# TargetBoardResistiveDivider.net
KiCad netlist of a schematic drawn in EAGLE
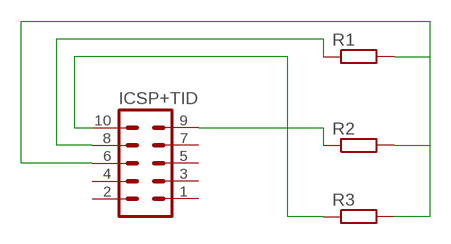
[diagram p0: schematic, sheet 1]

(export (version "E")
  (design (tool "Eeschema 10.0.6"))
  (components
    (comp (ref "ICSP+TID")
      (value "MA05-2")
      (footprint "eagle-import:MA05-2")
      (libsource (lib "eagle-import") (part "MA05-2"))
    )
    (comp (ref "R1")
      (value "R-EU_R1206")
      (footprint "eagle-import:R1206")
      (libsource (lib "eagle-import") (part "R-EU_R1206"))
    )
    (comp (ref "R2")
      (value "R-EU_R1206")
      (footprint "eagle-import:R1206")
      (libsource (lib "eagle-import") (part "R-EU_R1206"))
    )
    (comp (ref "R3")
      (value "R-EU_R1206")
      (footprint "eagle-import:R1206")
      (libsource (lib "eagle-import") (part "R-EU_R1206"))
    )
  )
  (nets
    (net (code "1") (name "Net-(ICSP+TID-Pad6)") (class "Default")
      (node (ref "ICSP+TID") (pin "6") (pinfunction "6_6") (pintype "passive"))
      (node (ref "R1") (pin "2") (pinfunction "2_2") (pintype "passive"))
      (node (ref "R2") (pin "2") (pinfunction "2_2") (pintype "passive"))
      (node (ref "R3") (pin "2") (pinfunction "2_2") (pintype "passive"))
    )
    (net (code "2") (name "Net-(ICSP+TID-Pad8)") (class "Default")
      (node (ref "ICSP+TID") (pin "8") (pinfunction "8_8") (pintype "passive"))
      (node (ref "R1") (pin "1") (pinfunction "1_1") (pintype "passive"))
    )
    (net (code "3") (name "Net-(ICSP+TID-Pad9)") (class "Default")
      (node (ref "ICSP+TID") (pin "9") (pinfunction "9_9") (pintype "passive"))
      (node (ref "R2") (pin "1") (pinfunction "1_1") (pintype "passive"))
    )
    (net (code "4") (name "Net-(ICSP+TID-Pad10)") (class "Default")
      (node (ref "ICSP+TID") (pin "10") (pinfunction "10_10") (pintype "passive"))
      (node (ref "R3") (pin "1") (pinfunction "1_1") (pintype "passive"))
    )
    (net (code "5") (name "unconnected-(ICSP+TID-Pad1)") (class "Default")
      (node (ref "ICSP+TID") (pin "1") (pinfunction "1_1") (pintype "passive"))
    )
    (net (code "6") (name "unconnected-(ICSP+TID-Pad2)") (class "Default")
      (node (ref "ICSP+TID") (pin "2") (pinfunction "2_2") (pintype "passive"))
    )
    (net (code "7") (name "unconnected-(ICSP+TID-Pad3)") (class "Default")
      (node (ref "ICSP+TID") (pin "3") (pinfunction "3_3") (pintype "passive"))
    )
    (net (code "8") (name "unconnected-(ICSP+TID-Pad4)") (class "Default")
      (node (ref "ICSP+TID") (pin "4") (pinfunction "4_4") (pintype "passive"))
    )
    (net (code "9") (name "unconnected-(ICSP+TID-Pad5)") (class "Default")
      (node (ref "ICSP+TID") (pin "5") (pinfunction "5_5") (pintype "passive"))
    )
    (net (code "10") (name "unconnected-(ICSP+TID-Pad7)") (class "Default")
      (node (ref "ICSP+TID") (pin "7") (pinfunction "7_7") (pintype "passive"))
    )
  )
)
